# sbc_smps_v0001.net
KiCad netlist of a schematic drawn in EAGLE
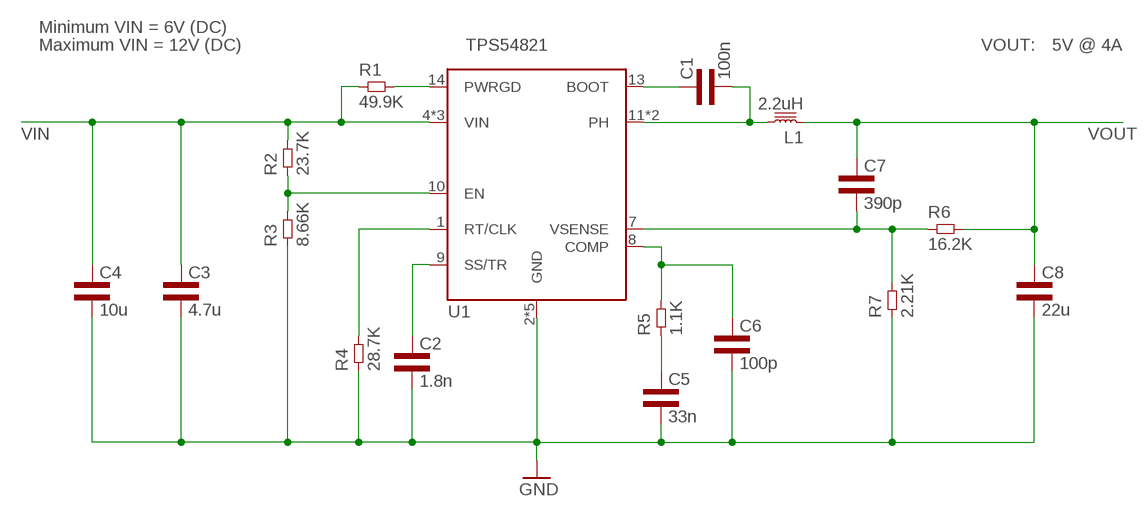
[diagram p0: schematic, sheet 1]

(export (version "E")
  (design (tool "Eeschema 10.0.6"))
  (components
    (comp (ref "C1")
      (value "100n")
      (footprint "eagle-import:0603L3")
      (libsource (lib "eagle-import") (part "CAP0603L3"))
    )
    (comp (ref "C2")
      (value "1.8n")
      (footprint "eagle-import:0402L3")
      (libsource (lib "eagle-import") (part "CAP0402L3"))
    )
    (comp (ref "C3")
      (value "4.7u")
      (footprint "eagle-import:0805L3")
      (libsource (lib "eagle-import") (part "CAP0805L3"))
    )
    (comp (ref "C4")
      (value "10u")
      (footprint "eagle-import:1206L3")
      (libsource (lib "eagle-import") (part "CAP1206L3"))
    )
    (comp (ref "C5")
      (value "33n")
      (footprint "eagle-import:0402L3")
      (libsource (lib "eagle-import") (part "CAP0402L3"))
    )
    (comp (ref "C6")
      (value "100p")
      (footprint "eagle-import:0402L3")
      (libsource (lib "eagle-import") (part "CAP0402L3"))
    )
    (comp (ref "C7")
      (value "390p")
      (footprint "eagle-import:0402L3")
      (libsource (lib "eagle-import") (part "CAP0402L3"))
    )
    (comp (ref "C8")
      (value "22u")
      (footprint "eagle-import:1206L3")
      (libsource (lib "eagle-import") (part "CAP1206L3"))
    )
    (comp (ref "L1")
      (value "2.2uH")
      (footprint "eagle-import:5.7X5.2")
      (libsource (lib "eagle-import") (part "INDUCTOR5752"))
    )
    (comp (ref "R1")
      (value "49.9K")
      (footprint "eagle-import:0402L3")
      (libsource (lib "eagle-import") (part "RES0402L3"))
    )
    (comp (ref "R2")
      (value "23.7K")
      (footprint "eagle-import:0402L3")
      (libsource (lib "eagle-import") (part "RES0402L3"))
    )
    (comp (ref "R3")
      (value "8.66K")
      (footprint "eagle-import:0402L3")
      (libsource (lib "eagle-import") (part "RES0402L3"))
    )
    (comp (ref "R4")
      (value "28.7K")
      (footprint "eagle-import:0402L3")
      (libsource (lib "eagle-import") (part "RES0402L3"))
    )
    (comp (ref "R5")
      (value "1.1K")
      (footprint "eagle-import:0402L3")
      (libsource (lib "eagle-import") (part "RES0402L3"))
    )
    (comp (ref "R6")
      (value "16.2K")
      (footprint "eagle-import:0402L3")
      (libsource (lib "eagle-import") (part "RES0402L3"))
    )
    (comp (ref "R7")
      (value "2.21K")
      (footprint "eagle-import:0402L3")
      (libsource (lib "eagle-import") (part "RES0402L3"))
    )
    (comp (ref "U1")
      (value "TPS54821")
      (footprint "eagle-import:VQFN-14")
      (libsource (lib "eagle-import") (part "TPS54821"))
    )
  )
  (nets
    (net (code "1") (name "/VIN") (class "Default")
      (node (ref "C3") (pin "1") (pinfunction "1_1") (pintype "bidirectional"))
      (node (ref "C4") (pin "1") (pinfunction "1_1") (pintype "bidirectional"))
      (node (ref "R1") (pin "P$1") (pinfunction "1_P$1") (pintype "bidirectional"))
      (node (ref "R2") (pin "P$2") (pinfunction "2_P$2") (pintype "bidirectional"))
      (node (ref "U1") (pin "4") (pinfunction "VIN_4") (pintype "bidirectional"))
      (node (ref "U1") (pin "5") (pinfunction "VIN_5") (pintype "bidirectional"))
      (node (ref "U1") (pin "6") (pinfunction "VIN_6") (pintype "bidirectional"))
    )
    (net (code "2") (name "/VOUT") (class "Default")
      (node (ref "C7") (pin "P$1") (pinfunction "1_P$1") (pintype "bidirectional"))
      (node (ref "C8") (pin "1") (pinfunction "1_1") (pintype "bidirectional"))
      (node (ref "L1") (pin "1") (pinfunction "1_1") (pintype "bidirectional"))
      (node (ref "R6") (pin "P$2") (pinfunction "2_P$2") (pintype "bidirectional"))
    )
    (net (code "3") (name "GND") (class "Default")
      (node (ref "C2") (pin "P$2") (pinfunction "2_P$2") (pintype "bidirectional"))
      (node (ref "C3") (pin "2") (pinfunction "2_2") (pintype "bidirectional"))
      (node (ref "C4") (pin "2") (pinfunction "2_2") (pintype "bidirectional"))
      (node (ref "C5") (pin "P$2") (pinfunction "2_P$2") (pintype "bidirectional"))
      (node (ref "C6") (pin "P$2") (pinfunction "2_P$2") (pintype "bidirectional"))
      (node (ref "C8") (pin "2") (pinfunction "2_2") (pintype "bidirectional"))
      (node (ref "R3") (pin "P$1") (pinfunction "1_P$1") (pintype "bidirectional"))
      (node (ref "R4") (pin "P$1") (pinfunction "1_P$1") (pintype "bidirectional"))
      (node (ref "R7") (pin "P$1") (pinfunction "1_P$1") (pintype "bidirectional"))
      (node (ref "U1") (pin "2") (pinfunction "GND_2") (pintype "bidirectional"))
      (node (ref "U1") (pin "3") (pinfunction "GND_3") (pintype "bidirectional"))
      (node (ref "U1") (pin "TP@1") (pinfunction "GND_TP@1") (pintype "bidirectional"))
      (node (ref "U1") (pin "TP@2") (pinfunction "GND_TP@2") (pintype "bidirectional"))
      (node (ref "U1") (pin "TP@3") (pinfunction "GND_TP@3") (pintype "bidirectional"))
    )
    (net (code "4") (name "Net-(C1-1)") (class "Default")
      (node (ref "C1") (pin "P$1") (pinfunction "1_P$1") (pintype "bidirectional"))
      (node (ref "U1") (pin "13") (pinfunction "BOOT_13") (pintype "bidirectional"))
    )
    (net (code "5") (name "Net-(C1-2)") (class "Default")
      (node (ref "C1") (pin "P$2") (pinfunction "2_P$2") (pintype "bidirectional"))
      (node (ref "L1") (pin "2") (pinfunction "2_2") (pintype "bidirectional"))
      (node (ref "U1") (pin "11") (pinfunction "PH_11") (pintype "bidirectional"))
      (node (ref "U1") (pin "12") (pinfunction "PH_12") (pintype "bidirectional"))
    )
    (net (code "6") (name "Net-(C2-1)") (class "Default")
      (node (ref "C2") (pin "P$1") (pinfunction "1_P$1") (pintype "bidirectional"))
      (node (ref "U1") (pin "9") (pinfunction "SS/TR_9") (pintype "bidirectional"))
    )
    (net (code "7") (name "Net-(C5-1)") (class "Default")
      (node (ref "C5") (pin "P$1") (pinfunction "1_P$1") (pintype "bidirectional"))
      (node (ref "R5") (pin "P$1") (pinfunction "1_P$1") (pintype "bidirectional"))
    )
    (net (code "8") (name "Net-(C6-1)") (class "Default")
      (node (ref "C6") (pin "P$1") (pinfunction "1_P$1") (pintype "bidirectional"))
      (node (ref "R5") (pin "P$2") (pinfunction "2_P$2") (pintype "bidirectional"))
      (node (ref "U1") (pin "8") (pinfunction "COMP_8") (pintype "bidirectional"))
    )
    (net (code "9") (name "Net-(C7-2)") (class "Default")
      (node (ref "C7") (pin "P$2") (pinfunction "2_P$2") (pintype "bidirectional"))
      (node (ref "R6") (pin "P$1") (pinfunction "1_P$1") (pintype "bidirectional"))
      (node (ref "R7") (pin "P$2") (pinfunction "2_P$2") (pintype "bidirectional"))
      (node (ref "U1") (pin "7") (pinfunction "VSENSE_7") (pintype "bidirectional"))
    )
    (net (code "10") (name "Net-(R1-2)") (class "Default")
      (node (ref "R1") (pin "P$2") (pinfunction "2_P$2") (pintype "bidirectional"))
      (node (ref "U1") (pin "14") (pinfunction "PWRGD_14") (pintype "bidirectional"))
    )
    (net (code "11") (name "Net-(R2-1)") (class "Default")
      (node (ref "R2") (pin "P$1") (pinfunction "1_P$1") (pintype "bidirectional"))
      (node (ref "R3") (pin "P$2") (pinfunction "2_P$2") (pintype "bidirectional"))
      (node (ref "U1") (pin "10") (pinfunction "EN_10") (pintype "bidirectional"))
    )
    (net (code "12") (name "Net-(R4-2)") (class "Default")
      (node (ref "R4") (pin "P$2") (pinfunction "2_P$2") (pintype "bidirectional"))
      (node (ref "U1") (pin "1") (pinfunction "RT/CLK_1") (pintype "bidirectional"))
    )
  )
)
